# Arduino_UNO_HuHu_tecnologies.net
KiCad netlist of a schematic drawn in EasyEDA
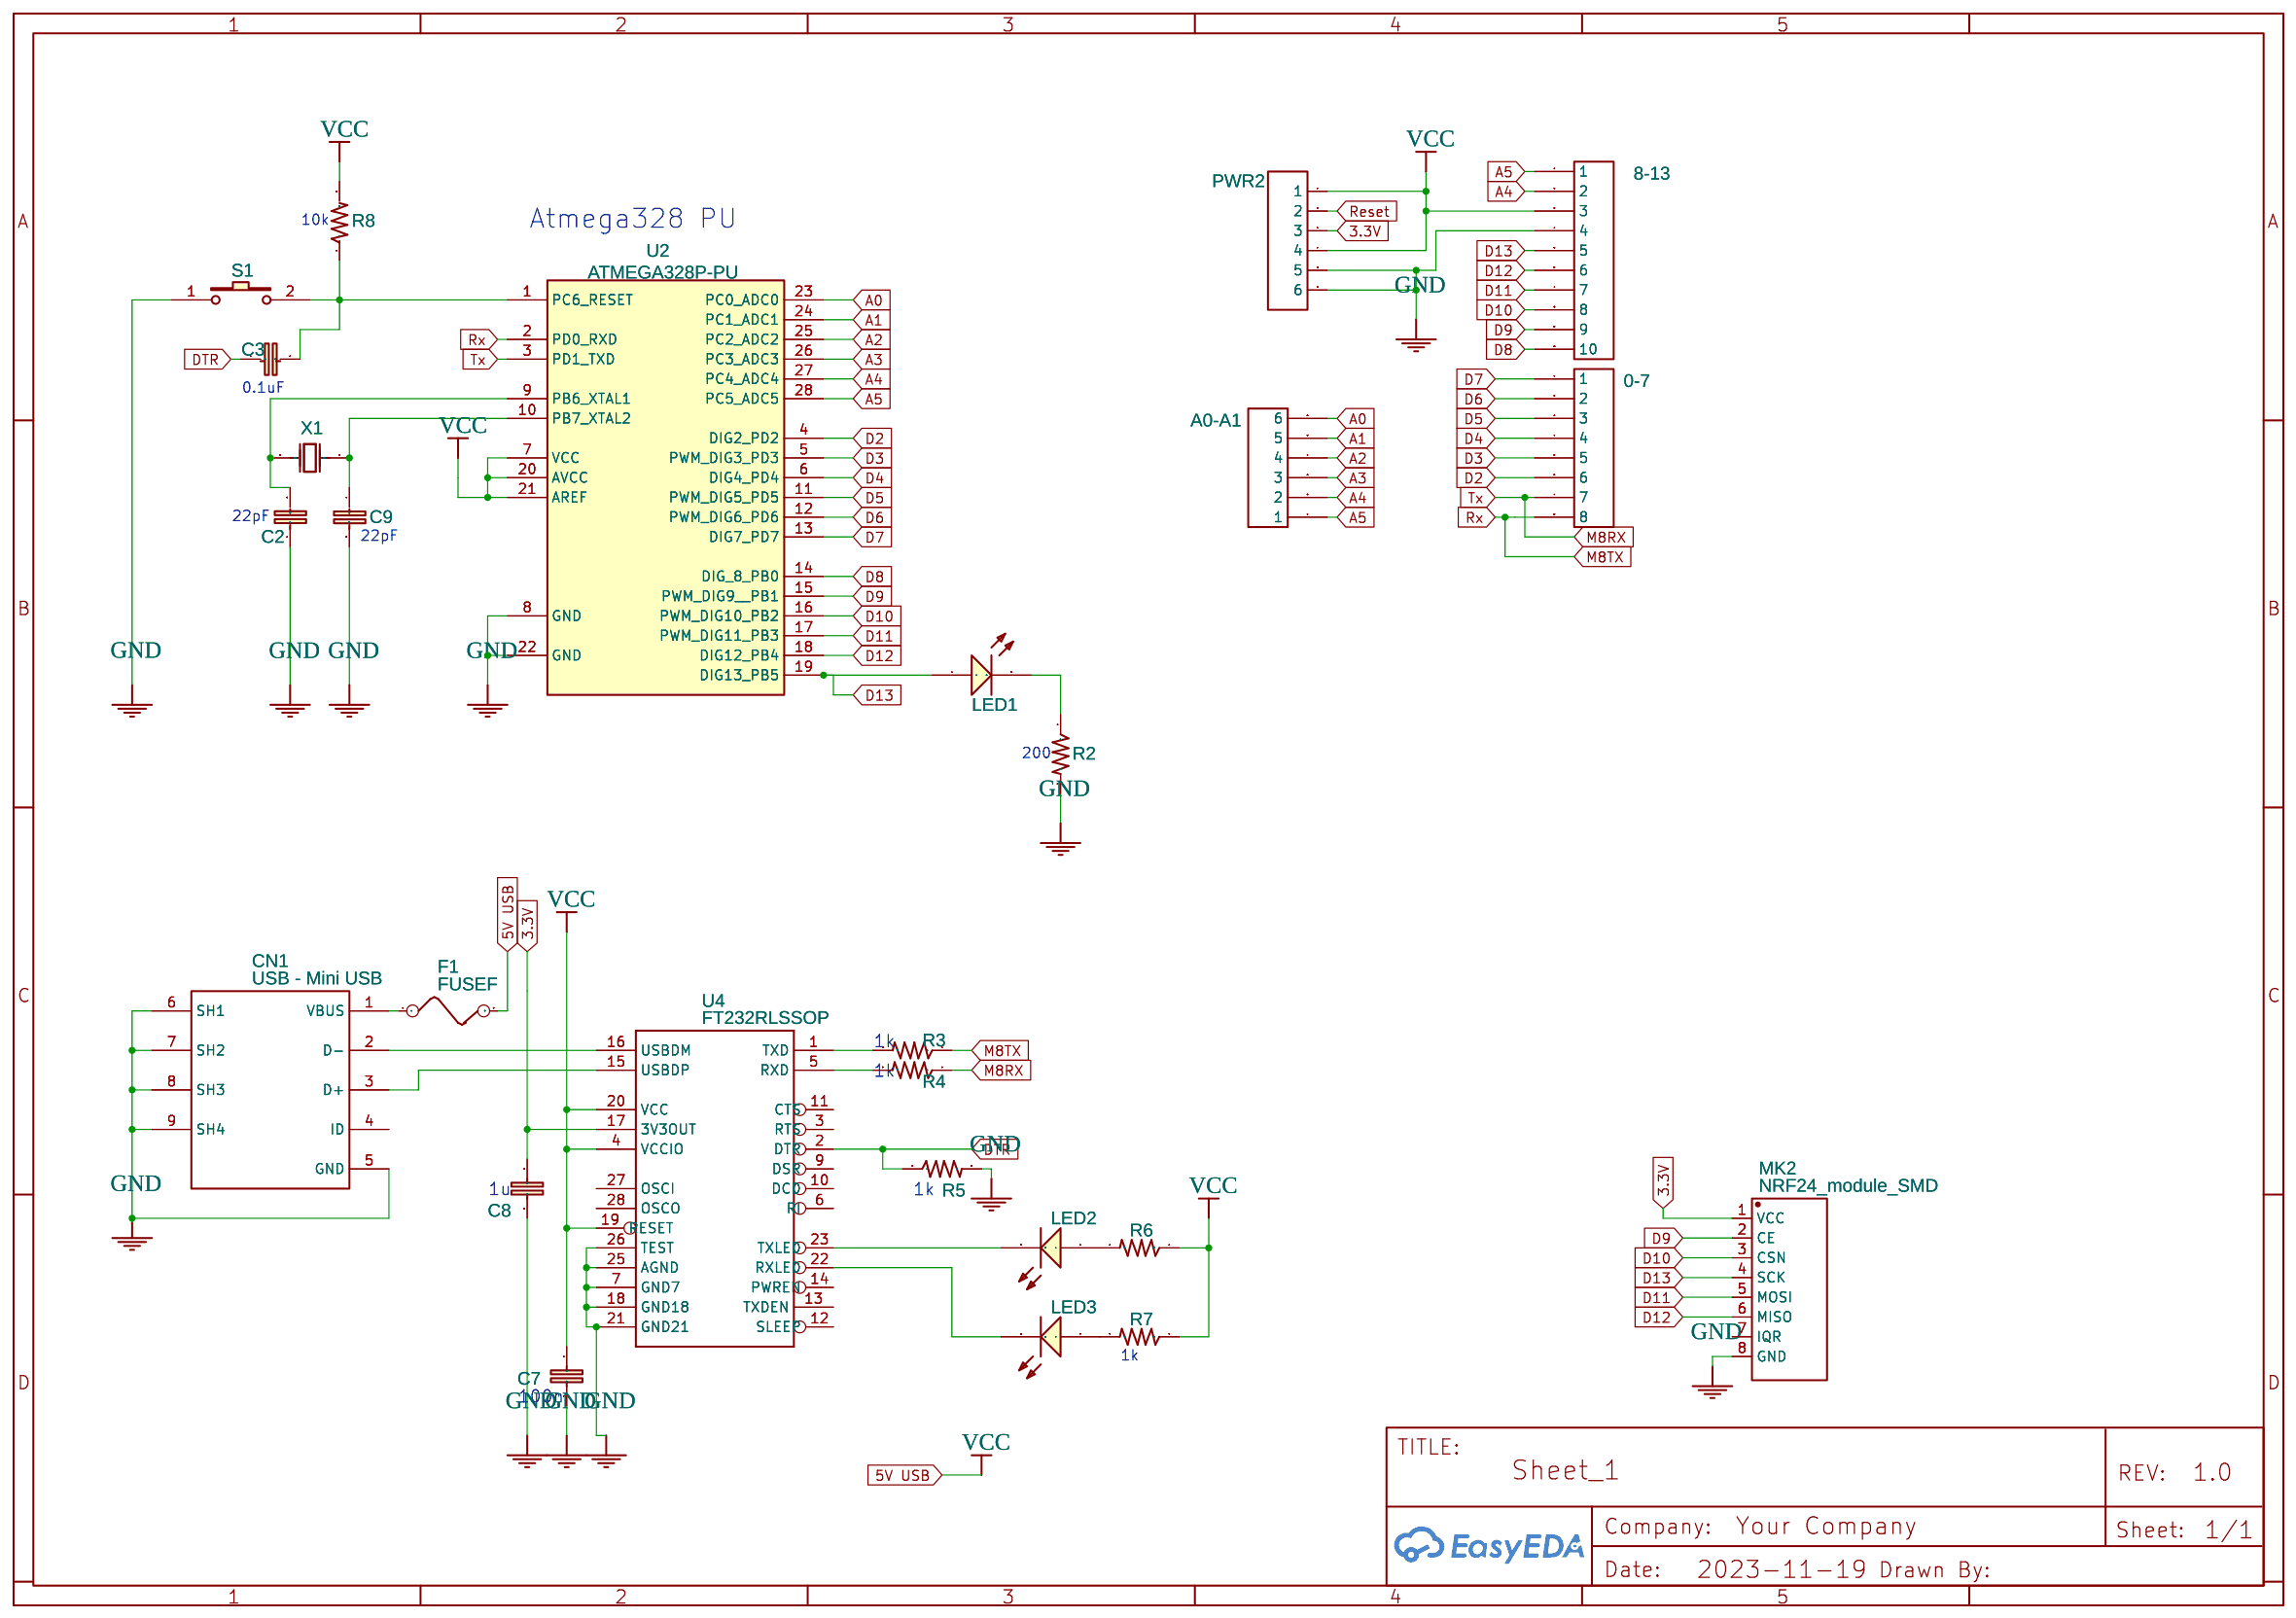
[diagram p0: schematic sheet]

(export (version "E")
  (design (tool "Eeschema 10.0.6"))
  (components
    (comp (ref "0-7")
      (value "0-7")
      (fields (field (name "Manufacturer Part") "Header2.54mm 1*8P") (field (name "Manufacturer") "ReliaPro"))
      (libsource (lib "") (part "Unknown_785_-590"))
    )
    (comp (ref "8-13")
      (value "8-Aref")
      (fields
        (field (name "Manufacturer Part") "Headers  Pins2.54mm1*10P")
        (field (name "Manufacturer") "ReliaPro")
      )
      (libsource (lib "") (part "Unknown_785_-685"))
    )
    (comp (ref "A0-A1")
      (value "Analogs")
      (fields
        (field (name "Manufacturer Part") "Header-Male-2.54_1x6")
        (field (name "Manufacturer") "BOOMELE")
      )
      (libsource (lib "") (part "Unknown_660_-570"))
    )
    (comp (ref "C2")
      (value "CAPACITOR_NPOL-0805")
      (fields (field (name "Manufacturer Part") "?"))
      (libsource (lib "") (part "Unknown_145_-555"))
    )
    (comp (ref "C3")
      (value "CAPACITOR_NPOL-0805")
      (fields (field (name "Manufacturer Part") "?"))
      (libsource (lib "") (part "Unknown_140_-630"))
    )
    (comp (ref "C7")
      (value "CAPACITOR_NPOL-0805")
      (fields (field (name "Manufacturer Part") "?"))
      (libsource (lib "") (part "Unknown_285_-110"))
    )
    (comp (ref "C8")
      (value "CAPACITOR_NPOL-0805")
      (fields (field (name "Manufacturer Part") "?"))
      (libsource (lib "") (part "Unknown_265_-205"))
    )
    (comp (ref "C9")
      (value "CAPACITOR_NPOL-0805")
      (fields (field (name "Manufacturer Part") "?"))
      (libsource (lib "") (part "Unknown_175_-545"))
    )
    (comp (ref "CN1") (value "USB - Mini USB") (libsource (lib "") (part "Unknown_135_-270")))
    (comp (ref "F1")
      (value "FUSEF")
      (fields (field (name "Manufacturer Part") "?"))
      (libsource (lib "") (part "Unknown_230_-300"))
    )
    (comp (ref "LED1")
      (value "17-21/GHC-YR1S2/3T")
      (fields (field (name "Manufacturer") "EVERLIGHT"))
      (libsource (lib "") (part "Unknown_490_-470"))
    )
    (comp (ref "LED2")
      (value "17-21/GHC-YR1S2/3T")
      (fields (field (name "Manufacturer") "EVERLIGHT"))
      (libsource (lib "") (part "Unknown_535_-180"))
    )
    (comp (ref "LED3")
      (value "17-21/GHC-YR1S2/3T")
      (fields (field (name "Manufacturer") "EVERLIGHT"))
      (libsource (lib "") (part "Unknown_535_-135"))
    )
    (comp (ref "MK2")
      (value "NRF24_module_SMD")
      (fields (field (name "Manufacturer Part") "AS01-ML01S") (field (name "Manufacturer") "Ashining"))
      (libsource (lib "") (part "Unknown_885_-185"))
    )
    (comp (ref "PWR2") (value "Power") (libsource (lib "") (part "HDR-F-2.54_1x6")))
    (comp (ref "R2")
      (value "200")
      (fields (field (name "Manufacturer Part") "?"))
      (libsource (lib "") (part "Unknown_535_-430"))
    )
    (comp (ref "R3")
      (value "200")
      (fields (field (name "Manufacturer Part") "?"))
      (libsource (lib "") (part "Unknown_460_-280"))
    )
    (comp (ref "R4")
      (value "200")
      (fields (field (name "Manufacturer Part") "?"))
      (libsource (lib "") (part "Unknown_460_-270"))
    )
    (comp (ref "R5")
      (value "200")
      (fields (field (name "Manufacturer Part") "?"))
      (libsource (lib "") (part "Unknown_475_-220"))
    )
    (comp (ref "R6")
      (value "200")
      (fields (field (name "Manufacturer Part") "?"))
      (libsource (lib "") (part "Unknown_575_-180"))
    )
    (comp (ref "R7")
      (value "200")
      (fields (field (name "Manufacturer Part") "?"))
      (libsource (lib "") (part "Unknown_575_-135"))
    )
    (comp (ref "R8")
      (value "0.22OHM-1_4W-1%(0805)")
      (fields (field (name "Manufacturer Part") "?"))
      (libsource (lib "") (part "Unknown_170_-700"))
    )
    (comp (ref "S1")
      (value "Button1")
      (fields (field (name "Manufacturer Part") "?"))
      (libsource (lib "") (part "Unknown_115_-660"))
    )
    (comp (ref "U2")
      (value "ATMEGA328P-PU")
      (fields (field (name "Manufacturer") "ATMEL"))
      (libsource (lib "") (part "Unknown_315_-540"))
    )
    (comp (ref "U4")
      (value "FT232RLSSOP")
      (fields (field (name "Manufacturer Part") "?"))
      (libsource (lib "") (part "Unknown_360_-210"))
    )
    (comp (ref "X1")
      (value "16MHZ")
      (fields (field (name "Manufacturer Part") "X49SD16MSD2SC") (field (name "Manufacturer") "YXC"))
      (libsource (lib "") (part "Unknown_155_-580"))
    )
  )
  (nets
    (net (code "1") (name "3.3V") (class "Default")
      (node (ref "C8") (pin "1") (pinfunction "1_1") (pintype "unspecified"))
      (node (ref "MK2") (pin "1") (pinfunction "VCC_1") (pintype "unspecified"))
      (node (ref "PWR2") (pin "3") (pinfunction "3_3") (pintype "input"))
      (node (ref "U4") (pin "17") (pinfunction "3V3OUT_17") (pintype "output"))
    )
    (net (code "2") (name "5V USB") (class "Default")
      (node (ref "8-13") (pin "3") (pinfunction "3_3") (pintype "input"))
      (node (ref "C7") (pin "1") (pinfunction "1_1") (pintype "unspecified"))
      (node (ref "F1") (pin "2") (pinfunction "2_2") (pintype "unspecified"))
      (node (ref "PWR2") (pin "1") (pinfunction "1_1") (pintype "input"))
      (node (ref "PWR2") (pin "4") (pinfunction "4_4") (pintype "input"))
      (node (ref "R6") (pin "1") (pinfunction "1_1") (pintype "unspecified"))
      (node (ref "R7") (pin "1") (pinfunction "1_1") (pintype "unspecified"))
      (node (ref "R8") (pin "2") (pinfunction "2_2") (pintype "unspecified"))
      (node (ref "U2") (pin "20") (pinfunction "AVCC_20") (pintype "passive"))
      (node (ref "U2") (pin "21") (pinfunction "AREF_21") (pintype "passive"))
      (node (ref "U2") (pin "7") (pinfunction "VCC_7") (pintype "passive"))
      (node (ref "U4") (pin "19") (pinfunction "RESET_19") (pintype "input"))
      (node (ref "U4") (pin "20") (pinfunction "VCC_20") (pintype "passive"))
      (node (ref "U4") (pin "4") (pinfunction "VCCIO_4") (pintype "passive"))
    )
    (net (code "3") (name "A0") (class "Default")
      (node (ref "A0-A1") (pin "6") (pinfunction "6_6") (pintype "input"))
      (node (ref "U2") (pin "23") (pinfunction "PC0_ADC0_23") (pintype "bidirectional"))
    )
    (net (code "4") (name "A1") (class "Default")
      (node (ref "A0-A1") (pin "5") (pinfunction "5_5") (pintype "input"))
      (node (ref "U2") (pin "24") (pinfunction "PC1_ADC1_24") (pintype "bidirectional"))
    )
    (net (code "5") (name "A2") (class "Default")
      (node (ref "A0-A1") (pin "4") (pinfunction "4_4") (pintype "input"))
      (node (ref "U2") (pin "25") (pinfunction "PC2_ADC2_25") (pintype "bidirectional"))
    )
    (net (code "6") (name "A3") (class "Default")
      (node (ref "A0-A1") (pin "3") (pinfunction "3_3") (pintype "input"))
      (node (ref "U2") (pin "26") (pinfunction "PC3_ADC3_26") (pintype "bidirectional"))
    )
    (net (code "7") (name "A4") (class "Default")
      (node (ref "8-13") (pin "2") (pinfunction "2_2") (pintype "input"))
      (node (ref "A0-A1") (pin "2") (pinfunction "2_2") (pintype "input"))
      (node (ref "U2") (pin "27") (pinfunction "PC4_ADC4_27") (pintype "bidirectional"))
    )
    (net (code "8") (name "A5") (class "Default")
      (node (ref "8-13") (pin "1") (pinfunction "1_1") (pintype "input"))
      (node (ref "A0-A1") (pin "1") (pinfunction "1_1") (pintype "input"))
      (node (ref "U2") (pin "28") (pinfunction "PC5_ADC5_28") (pintype "bidirectional"))
    )
    (net (code "9") (name "D2") (class "Default")
      (node (ref "0-7") (pin "6") (pinfunction "6_6") (pintype "input"))
      (node (ref "U2") (pin "4") (pinfunction "DIG2_PD2_4") (pintype "bidirectional"))
    )
    (net (code "10") (name "D3") (class "Default")
      (node (ref "0-7") (pin "5") (pinfunction "5_5") (pintype "input"))
      (node (ref "U2") (pin "5") (pinfunction "PWM_DIG3_PD3_5") (pintype "bidirectional"))
    )
    (net (code "11") (name "D4") (class "Default")
      (node (ref "0-7") (pin "4") (pinfunction "4_4") (pintype "input"))
      (node (ref "U2") (pin "6") (pinfunction "DIG4_PD4_6") (pintype "bidirectional"))
    )
    (net (code "12") (name "D5") (class "Default")
      (node (ref "0-7") (pin "3") (pinfunction "3_3") (pintype "input"))
      (node (ref "U2") (pin "11") (pinfunction "PWM_DIG5_PD5_11") (pintype "bidirectional"))
    )
    (net (code "13") (name "D6") (class "Default")
      (node (ref "0-7") (pin "2") (pinfunction "2_2") (pintype "input"))
      (node (ref "U2") (pin "12") (pinfunction "PWM_DIG6_PD6_12") (pintype "bidirectional"))
    )
    (net (code "14") (name "D7") (class "Default")
      (node (ref "0-7") (pin "1") (pinfunction "1_1") (pintype "input"))
      (node (ref "U2") (pin "13") (pinfunction "DIG7_PD7_13") (pintype "bidirectional"))
    )
    (net (code "15") (name "D8") (class "Default")
      (node (ref "8-13") (pin "10") (pinfunction "10_10") (pintype "input"))
      (node (ref "U2") (pin "14") (pinfunction "DIG_8_PB0_14") (pintype "bidirectional"))
    )
    (net (code "16") (name "D9") (class "Default")
      (node (ref "8-13") (pin "9") (pinfunction "9_9") (pintype "input"))
      (node (ref "MK2") (pin "2") (pinfunction "CE_2") (pintype "unspecified"))
      (node (ref "U2") (pin "15") (pinfunction "PWM_DIG9__PB1_15") (pintype "bidirectional"))
    )
    (net (code "17") (name "D10") (class "Default")
      (node (ref "8-13") (pin "8") (pinfunction "8_8") (pintype "input"))
      (node (ref "MK2") (pin "3") (pinfunction "CSN_3") (pintype "unspecified"))
      (node (ref "U2") (pin "16") (pinfunction "PWM_DIG10_PB2_16") (pintype "bidirectional"))
    )
    (net (code "18") (name "D11") (class "Default")
      (node (ref "8-13") (pin "7") (pinfunction "7_7") (pintype "input"))
      (node (ref "MK2") (pin "5") (pinfunction "MOSI_5") (pintype "unspecified"))
      (node (ref "U2") (pin "17") (pinfunction "PWM_DIG11_PB3_17") (pintype "bidirectional"))
    )
    (net (code "19") (name "D12") (class "Default")
      (node (ref "8-13") (pin "6") (pinfunction "6_6") (pintype "input"))
      (node (ref "MK2") (pin "6") (pinfunction "MISO_6") (pintype "unspecified"))
      (node (ref "U2") (pin "18") (pinfunction "DIG12_PB4_18") (pintype "bidirectional"))
    )
    (net (code "20") (name "D13") (class "Default")
      (node (ref "8-13") (pin "5") (pinfunction "5_5") (pintype "input"))
      (node (ref "LED1") (pin "1") (pinfunction "A_1") (pintype "input"))
      (node (ref "MK2") (pin "4") (pinfunction "SCK_4") (pintype "unspecified"))
      (node (ref "U2") (pin "19") (pinfunction "DIG13_PB5_19") (pintype "bidirectional"))
    )
    (net (code "21") (name "DTR") (class "Default")
      (node (ref "C3") (pin "1") (pinfunction "1_1") (pintype "unspecified"))
      (node (ref "R5") (pin "1") (pinfunction "1_1") (pintype "unspecified"))
      (node (ref "U4") (pin "2") (pinfunction "DTR_2") (pintype "output"))
    )
    (net (code "22") (name "GND") (class "Default")
      (node (ref "8-13") (pin "4") (pinfunction "4_4") (pintype "input"))
      (node (ref "C2") (pin "1") (pinfunction "1_1") (pintype "unspecified"))
      (node (ref "C7") (pin "2") (pinfunction "2_2") (pintype "unspecified"))
      (node (ref "C8") (pin "2") (pinfunction "2_2") (pintype "unspecified"))
      (node (ref "C9") (pin "2") (pinfunction "2_2") (pintype "unspecified"))
      (node (ref "CN1") (pin "5") (pinfunction "GND_5") (pintype "passive"))
      (node (ref "CN1") (pin "6") (pinfunction "SH1_6") (pintype "passive"))
      (node (ref "CN1") (pin "7") (pinfunction "SH2_7") (pintype "passive"))
      (node (ref "CN1") (pin "8") (pinfunction "SH3_8") (pintype "passive"))
      (node (ref "CN1") (pin "9") (pinfunction "SH4_9") (pintype "passive"))
      (node (ref "MK2") (pin "8") (pinfunction "GND_8") (pintype "unspecified"))
      (node (ref "PWR2") (pin "5") (pinfunction "5_5") (pintype "input"))
      (node (ref "PWR2") (pin "6") (pinfunction "6_6") (pintype "input"))
      (node (ref "R2") (pin "2") (pinfunction "2_2") (pintype "unspecified"))
      (node (ref "R5") (pin "2") (pinfunction "2_2") (pintype "unspecified"))
      (node (ref "S1") (pin "1") (pintype "unspecified"))
      (node (ref "U2") (pin "22") (pinfunction "GND_22") (pintype "passive"))
      (node (ref "U2") (pin "8") (pinfunction "GND_8") (pintype "passive"))
      (node (ref "U4") (pin "18") (pinfunction "GND18_18") (pintype "passive"))
      (node (ref "U4") (pin "21") (pinfunction "GND21_21") (pintype "passive"))
      (node (ref "U4") (pin "25") (pinfunction "AGND_25") (pintype "passive"))
      (node (ref "U4") (pin "26") (pinfunction "TEST_26") (pintype "input"))
      (node (ref "U4") (pin "7") (pinfunction "GND7_7") (pintype "passive"))
    )
    (net (code "23") (name "M8RX") (class "Default")
      (node (ref "0-7") (pin "7") (pinfunction "7_7") (pintype "input"))
      (node (ref "R4") (pin "1") (pinfunction "1_1") (pintype "unspecified"))
      (node (ref "U2") (pin "3") (pinfunction "PD1_TXD_3") (pintype "bidirectional"))
    )
    (net (code "24") (name "M8TX") (class "Default")
      (node (ref "0-7") (pin "8") (pinfunction "8_8") (pintype "input"))
      (node (ref "R3") (pin "1") (pinfunction "1_1") (pintype "unspecified"))
      (node (ref "U2") (pin "2") (pinfunction "PD0_RXD_2") (pintype "bidirectional"))
    )
    (net (code "25") (name "Net-(CN1-D+)") (class "Default")
      (node (ref "CN1") (pin "3") (pinfunction "D+_3") (pintype "bidirectional"))
      (node (ref "U4") (pin "15") (pinfunction "USBDP_15") (pintype "unspecified"))
    )
    (net (code "26") (name "Net-(CN1-D-)") (class "Default")
      (node (ref "CN1") (pin "2") (pinfunction "D-_2") (pintype "bidirectional"))
      (node (ref "U4") (pin "16") (pinfunction "USBDM_16") (pintype "unspecified"))
    )
    (net (code "27") (name "Net-(CN1-VBUS)") (class "Default")
      (node (ref "CN1") (pin "1") (pinfunction "VBUS_1") (pintype "passive"))
      (node (ref "F1") (pin "1") (pinfunction "1_1") (pintype "unspecified"))
    )
    (net (code "28") (name "Net-(LED1-C)") (class "Default")
      (node (ref "LED1") (pin "2") (pinfunction "C_2") (pintype "input"))
      (node (ref "R2") (pin "1") (pinfunction "1_1") (pintype "unspecified"))
    )
    (net (code "29") (name "Net-(LED2-A)") (class "Default")
      (node (ref "LED2") (pin "1") (pinfunction "A_1") (pintype "input"))
      (node (ref "R6") (pin "2") (pinfunction "2_2") (pintype "unspecified"))
    )
    (net (code "30") (name "Net-(LED2-C)") (class "Default")
      (node (ref "LED2") (pin "2") (pinfunction "C_2") (pintype "input"))
      (node (ref "U4") (pin "23") (pinfunction "TXLED_23") (pintype "input"))
    )
    (net (code "31") (name "Net-(LED3-A)") (class "Default")
      (node (ref "LED3") (pin "1") (pinfunction "A_1") (pintype "input"))
      (node (ref "R7") (pin "2") (pinfunction "2_2") (pintype "unspecified"))
    )
    (net (code "32") (name "Net-(LED3-C)") (class "Default")
      (node (ref "LED3") (pin "2") (pinfunction "C_2") (pintype "input"))
      (node (ref "U4") (pin "22") (pinfunction "RXLED_22") (pintype "input"))
    )
    (net (code "33") (name "Net-(U2-PB6_XTAL1)") (class "Default")
      (node (ref "C2") (pin "2") (pinfunction "2_2") (pintype "unspecified"))
      (node (ref "U2") (pin "9") (pinfunction "PB6_XTAL1_9") (pintype "bidirectional"))
      (node (ref "X1") (pin "2") (pinfunction "OSC2_2") (pintype "input"))
    )
    (net (code "34") (name "Net-(U2-PB7_XTAL2)") (class "Default")
      (node (ref "C9") (pin "1") (pinfunction "1_1") (pintype "unspecified"))
      (node (ref "U2") (pin "10") (pinfunction "PB7_XTAL2_10") (pintype "bidirectional"))
      (node (ref "X1") (pin "1") (pinfunction "OSC1_1") (pintype "input"))
    )
    (net (code "35") (name "Net-(U2-PC6_RESET)") (class "Default")
      (node (ref "C3") (pin "2") (pinfunction "2_2") (pintype "unspecified"))
      (node (ref "R8") (pin "1") (pinfunction "1_1") (pintype "unspecified"))
      (node (ref "S1") (pin "2") (pintype "unspecified"))
      (node (ref "U2") (pin "1") (pinfunction "PC6_RESET_1") (pintype "bidirectional"))
    )
    (net (code "36") (name "Net-(U4-RXD)") (class "Default")
      (node (ref "R4") (pin "2") (pinfunction "2_2") (pintype "unspecified"))
      (node (ref "U4") (pin "5") (pinfunction "RXD_5") (pintype "input"))
    )
    (net (code "37") (name "Net-(U4-TXD)") (class "Default")
      (node (ref "R3") (pin "2") (pinfunction "2_2") (pintype "unspecified"))
      (node (ref "U4") (pin "1") (pinfunction "TXD_1") (pintype "output"))
    )
    (net (code "38") (name "Reset") (class "Default")
      (node (ref "PWR2") (pin "2") (pinfunction "2_2") (pintype "input"))
    )
    (net (code "39") (name "unconnected-(CN1-ID-Pad4)") (class "Default")
      (node (ref "CN1") (pin "4") (pinfunction "ID_4") (pintype "bidirectional"))
    )
    (net (code "40") (name "unconnected-(MK2-IQR-Pad7)") (class "Default")
      (node (ref "MK2") (pin "7") (pinfunction "IQR_7") (pintype "unspecified"))
    )
    (net (code "41") (name "unconnected-(U4-CTS-Pad11)") (class "Default")
      (node (ref "U4") (pin "11") (pinfunction "CTS_11") (pintype "input"))
    )
    (net (code "42") (name "unconnected-(U4-DCD-Pad10)") (class "Default")
      (node (ref "U4") (pin "10") (pinfunction "DCD_10") (pintype "input"))
    )
    (net (code "43") (name "unconnected-(U4-DSR-Pad9)") (class "Default")
      (node (ref "U4") (pin "9") (pinfunction "DSR_9") (pintype "input"))
    )
    (net (code "44") (name "unconnected-(U4-OSCI-Pad27)") (class "Default")
      (node (ref "U4") (pin "27") (pinfunction "OSCI_27") (pintype "input"))
    )
    (net (code "45") (name "unconnected-(U4-OSCO-Pad28)") (class "Default")
      (node (ref "U4") (pin "28") (pinfunction "OSCO_28") (pintype "output"))
    )
    (net (code "46") (name "unconnected-(U4-PWREN-Pad14)") (class "Default")
      (node (ref "U4") (pin "14") (pinfunction "PWREN_14") (pintype "input"))
    )
    (net (code "47") (name "unconnected-(U4-RI-Pad6)") (class "Default")
      (node (ref "U4") (pin "6") (pinfunction "RI_6") (pintype "input"))
    )
    (net (code "48") (name "unconnected-(U4-RTS-Pad3)") (class "Default")
      (node (ref "U4") (pin "3") (pinfunction "RTS_3") (pintype "output"))
    )
    (net (code "49") (name "unconnected-(U4-SLEEP-Pad12)") (class "Default")
      (node (ref "U4") (pin "12") (pinfunction "SLEEP_12") (pintype "input"))
    )
    (net (code "50") (name "unconnected-(U4-TXDEN-Pad13)") (class "Default")
      (node (ref "U4") (pin "13") (pinfunction "TXDEN_13") (pintype "input"))
    )
  )
)
